# Sheet1.net
KiCad netlist of a schematic drawn in Altium Designer
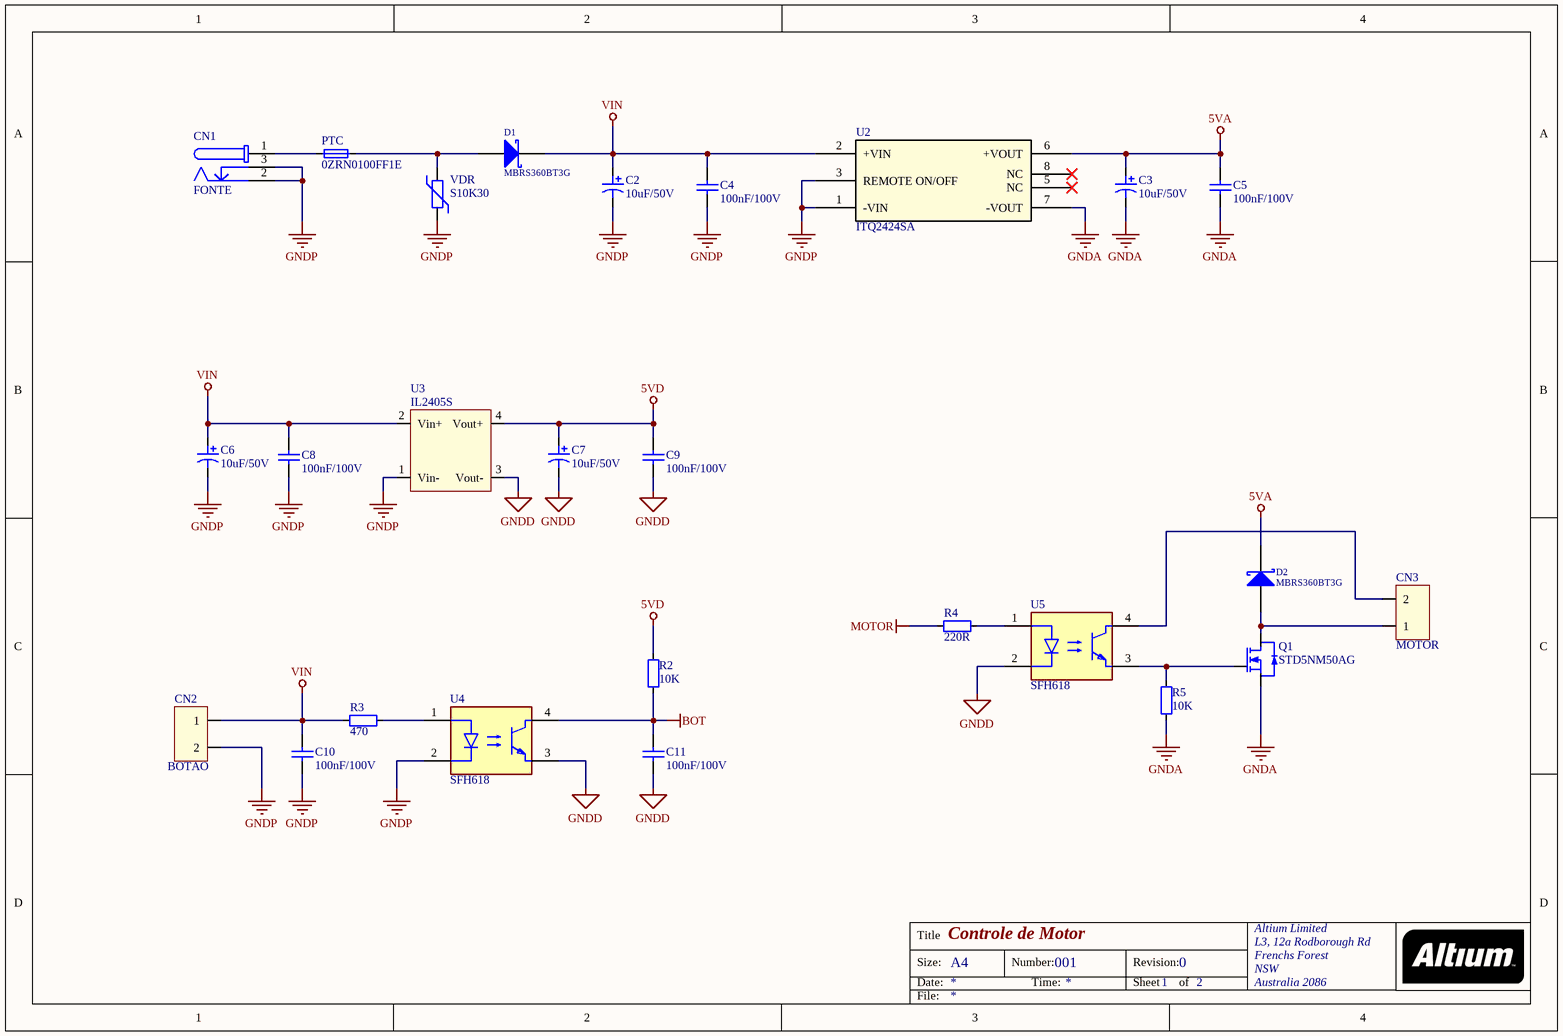
[diagram p0: Sheet1.SchDoc]

(export (version "E")
  (design (tool "Eeschema 10.0.6"))
  (components
    (comp (ref "C2")
      (value "10uF/50V")
      (footprint "CapE SMD D6.3 L5.8")
      (description "Capacitor Eletrolítico Radial SMD")
      (libsource (lib "Schlib") (part "Cap Eletrolitico"))
    )
    (comp (ref "C3")
      (value "10uF/50V")
      (footprint "CapE SMD D6.3 L5.8")
      (description "Capacitor Eletrolítico Radial SMD")
      (libsource (lib "Schlib") (part "Cap Eletrolitico"))
    )
    (comp (ref "C4")
      (value "100nF/100V")
      (footprint "0603C-GENERIC")
      (description "Capacitor Cerâmico SMD")
      (libsource (lib "Schlib") (part "Cap Ceramico SMD"))
    )
    (comp (ref "C5")
      (value "100nF/100V")
      (footprint "0603C-GENERIC")
      (description "Capacitor Cerâmico SMD")
      (libsource (lib "Schlib") (part "Cap Ceramico SMD"))
    )
    (comp (ref "C6")
      (value "10uF/50V")
      (footprint "CapE SMD D6.3 L5.8")
      (description "Capacitor Eletrolítico Radial SMD")
      (libsource (lib "Schlib") (part "Cap Eletrolitico"))
    )
    (comp (ref "C7")
      (value "10uF/50V")
      (footprint "CapE SMD D6.3 L5.8")
      (description "Capacitor Eletrolítico Radial SMD")
      (libsource (lib "Schlib") (part "Cap Eletrolitico"))
    )
    (comp (ref "C8")
      (value "100nF/100V")
      (footprint "0603C-GENERIC")
      (description "Capacitor Cerâmico SMD")
      (libsource (lib "Schlib") (part "Cap Ceramico SMD"))
    )
    (comp (ref "C9")
      (value "100nF/100V")
      (footprint "0603C-GENERIC")
      (description "Capacitor Cerâmico SMD")
      (libsource (lib "Schlib") (part "Cap Ceramico SMD"))
    )
    (comp (ref "C10")
      (value "100nF/100V")
      (footprint "0603C-GENERIC")
      (description "Capacitor Cerâmico SMD")
      (libsource (lib "Schlib") (part "Cap Ceramico SMD"))
    )
    (comp (ref "C11")
      (value "100nF/100V")
      (footprint "0603C-GENERIC")
      (description "Capacitor Cerâmico SMD")
      (libsource (lib "Schlib") (part "Cap Ceramico SMD"))
    )
    (comp (ref "CN1")
      (value "FONTE")
      (footprint "Power Jack 694106301002")
      (description "DC Power Jack")
      (fields (field (name "PART NUMBER") "694106301002"))
      (libsource (lib "PUR Conectores") (part "DC Power Jack"))
    )
    (comp (ref "CN2")
      (value "BORNE")
      (footprint "AKZ700/2")
      (description "2 pinos")
      (libsource (lib "") (part "1x2 Pinos_1"))
    )
    (comp (ref "CN3")
      (value "BORNE")
      (footprint "AKZ700/2")
      (description "2 pinos")
      (libsource (lib "PUR Conectores") (part "1x2 Pinos"))
    )
    (comp (ref "D1")
      (value "MBRS360BT3G")
      (footprint "DO-214AA(SMB)")
      (description "Schottky Barrier Diode")
      (libsource (lib "Schlib") (part "BAT54"))
    )
    (comp (ref "D2")
      (value "MBRS360BT3G")
      (footprint "DO-214AA(SMB)")
      (description "Schottky Barrier Diode")
      (libsource (lib "Schlib") (part "BAT54"))
    )
    (comp (ref "PTC")
      (value "0ZRN0100FF1E")
      (footprint "PTC LVR")
      (description "Fusível Thermistor PTC")
      (libsource (lib "PUR Geral") (part "LVR008N"))
    )
    (comp (ref "Q1")
      (value "STD5NM50AG")
      (footprint "DPAK-3_ONS")
      (description "Transistor N-Channel")
      (libsource (lib "PUR Geral") (part "BSS138"))
    )
    (comp (ref "R2")
      (value "10K")
      (footprint "0603R")
      (description "Resistor Metal Filme")
      (libsource (lib "") (part "Res SMD 1206_2"))
    )
    (comp (ref "R3")
      (value "470")
      (footprint "Res 1206")
      (description "Resistor Metal Filme")
      (libsource (lib "") (part "Res SMD 1206_1"))
    )
    (comp (ref "R4")
      (value "220R")
      (footprint "0603R")
      (description "Resistor Metal Filme")
      (libsource (lib "Database_PUR") (part "Res SMD 1206"))
    )
    (comp (ref "R5")
      (value "10K")
      (footprint "0603R")
      (description "Resistor Metal Filme")
      (libsource (lib "") (part "Res SMD 1206_2"))
    )
    (comp (ref "U2")
      (value "ITQ2424SA")
      (footprint "SIP8_ITQ2424_XPR")
      (description "No Description Available")
      (fields (field (name "COPYRIGHT") "Copyright (C) 2026 Ultra Librarian. All rights reserved."))
      (libsource (lib "Schlib") (part "ITQ2424SA"))
    )
    (comp (ref "U3")
      (value "IL2405S")
      (footprint "IL SERIES")
      (description "Conversor DC/DC 2W")
      (fields (field (name "PART NUMBER") "E2CONV0000006"))
      (libsource (lib "PUR Geral") (part "IL2405S"))
    )
    (comp (ref "U4")
      (value "SFH618")
      (footprint "FP-83911-MFG")
      (description "Optocoupler Dc-in 1-CH Transistor Dc-out 4-PIN PDIP SMD T/r")
      (libsource (lib "PUR Equipamentos Industriais") (part "aa71ce9e162979105c9edb12a8cdbcc"))
    )
    (comp (ref "U5")
      (value "SFH618")
      (footprint "FP-83911-MFG")
      (description "Optocoupler Dc-in 1-CH Transistor Dc-out 4-PIN PDIP SMD T/r")
      (libsource (lib "PUR Equipamentos Industriais") (part "aa71ce9e162979105c9edb12a8cdbcc"))
    )
    (comp (ref "VDR")
      (value "S10K30")
      (footprint "VDR D12H14.5-7.5")
      (description "Varistor 30VAC/48VDC")
      (libsource (lib "PUR Geral") (part "VDR 1000L160"))
    )
  )
  (nets
    (net (code "1") (name "5VA") (class "Default")
      (node (ref "C3") (pin "1") (pinfunction "+_1") (pintype "passive"))
      (node (ref "C5") (pin "2") (pinfunction "2_2") (pintype "passive"))
      (node (ref "D2") (pin "2") (pinfunction "K_2") (pintype "passive"))
      (node (ref "U2") (pin "6") (pinfunction "+VOUT_6") (pintype "power_in"))
    )
    (net (code "2") (name "5VD") (class "Default")
      (node (ref "C7") (pin "1") (pinfunction "+_1") (pintype "passive"))
      (node (ref "C9") (pin "2") (pinfunction "2_2") (pintype "passive"))
      (node (ref "R2") (pin "1") (pinfunction "1_1") (pintype "passive"))
      (node (ref "U3") (pin "4") (pinfunction "Vout+_4") (pintype "passive"))
    )
    (net (code "3") (name "BOT") (class "Default")
      (node (ref "C11") (pin "2") (pinfunction "2_2") (pintype "passive"))
      (node (ref "R2") (pin "2") (pinfunction "2_2") (pintype "passive"))
      (node (ref "U4") (pin "4") (pinfunction "C_4") (pintype "passive"))
    )
    (net (code "4") (name "GNDA") (class "Default")
      (node (ref "C3") (pin "2") (pinfunction "-_2") (pintype "passive"))
      (node (ref "C5") (pin "1") (pinfunction "1_1") (pintype "passive"))
      (node (ref "Q1") (pin "2") (pinfunction "S_2") (pintype "passive"))
      (node (ref "R5") (pin "2") (pinfunction "2_2") (pintype "passive"))
      (node (ref "U2") (pin "7") (pinfunction "-VOUT_7") (pintype "power_in"))
    )
    (net (code "5") (name "GNDD") (class "Default")
      (node (ref "C11") (pin "1") (pinfunction "1_1") (pintype "passive"))
      (node (ref "C7") (pin "2") (pinfunction "-_2") (pintype "passive"))
      (node (ref "C9") (pin "1") (pinfunction "1_1") (pintype "passive"))
      (node (ref "U3") (pin "3") (pinfunction "Vout-_3") (pintype "passive"))
      (node (ref "U4") (pin "3") (pinfunction "E_3") (pintype "passive"))
      (node (ref "U5") (pin "2") (pinfunction "C_2") (pintype "passive"))
    )
    (net (code "6") (name "GNDP") (class "Default")
      (node (ref "C10") (pin "1") (pinfunction "1_1") (pintype "passive"))
      (node (ref "C2") (pin "2") (pinfunction "-_2") (pintype "passive"))
      (node (ref "C4") (pin "1") (pinfunction "1_1") (pintype "passive"))
      (node (ref "C6") (pin "2") (pinfunction "-_2") (pintype "passive"))
      (node (ref "C8") (pin "1") (pinfunction "1_1") (pintype "passive"))
      (node (ref "CN1") (pin "2") (pinfunction "2_2") (pintype "passive"))
      (node (ref "CN1") (pin "3") (pinfunction "3_3") (pintype "passive"))
      (node (ref "CN2") (pin "2") (pinfunction "2_2") (pintype "passive"))
      (node (ref "U2") (pin "1") (pinfunction "-VIN_1") (pintype "power_in"))
      (node (ref "U2") (pin "3") (pinfunction "REMOTE_ON/OFF_3") (pintype "passive"))
      (node (ref "U3") (pin "1") (pinfunction "Vin-_1") (pintype "passive"))
      (node (ref "U4") (pin "2") (pinfunction "C_2") (pintype "passive"))
      (node (ref "VDR") (pin "1") (pinfunction "1_1") (pintype "passive"))
    )
    (net (code "7") (name "MOTOR") (class "Default")
      (node (ref "R4") (pin "1") (pinfunction "1_1") (pintype "passive"))
    )
    (net (code "8") (name "Net-(CN1-Pad1)") (class "Default")
      (node (ref "CN1") (pin "1") (pinfunction "1_1") (pintype "passive"))
      (node (ref "PTC") (pin "1") (pintype "passive"))
    )
    (net (code "9") (name "Net-(CN3-Pad2)") (class "Default")
      (node (ref "CN3") (pin "2") (pinfunction "2_2") (pintype "passive"))
      (node (ref "U5") (pin "4") (pinfunction "C_4") (pintype "passive"))
    )
    (net (code "10") (name "Net-(D1-A)") (class "Default")
      (node (ref "D1") (pin "1") (pinfunction "A_1") (pintype "passive"))
      (node (ref "PTC") (pin "2") (pintype "passive"))
      (node (ref "VDR") (pin "2") (pinfunction "2_2") (pintype "passive"))
    )
    (net (code "11") (name "Net-(D2-A)") (class "Default")
      (node (ref "CN3") (pin "1") (pinfunction "1_1") (pintype "passive"))
      (node (ref "D2") (pin "1") (pinfunction "A_1") (pintype "passive"))
      (node (ref "Q1") (pin "3") (pinfunction "D_3") (pintype "passive"))
    )
    (net (code "12") (name "Net-(Q1-G)") (class "Default")
      (node (ref "Q1") (pin "1") (pinfunction "G_1") (pintype "passive"))
      (node (ref "R5") (pin "1") (pinfunction "1_1") (pintype "passive"))
      (node (ref "U5") (pin "3") (pinfunction "E_3") (pintype "passive"))
    )
    (net (code "13") (name "Net-(U4-A)") (class "Default")
      (node (ref "R3") (pin "1") (pinfunction "1_1") (pintype "passive"))
      (node (ref "U4") (pin "1") (pinfunction "A_1") (pintype "passive"))
    )
    (net (code "14") (name "Net-(U5-A)") (class "Default")
      (node (ref "R4") (pin "2") (pinfunction "2_2") (pintype "passive"))
      (node (ref "U5") (pin "1") (pinfunction "A_1") (pintype "passive"))
    )
    (net (code "15") (name "VIN") (class "Default")
      (node (ref "C10") (pin "2") (pinfunction "2_2") (pintype "passive"))
      (node (ref "C2") (pin "1") (pinfunction "+_1") (pintype "passive"))
      (node (ref "C4") (pin "2") (pinfunction "2_2") (pintype "passive"))
      (node (ref "C6") (pin "1") (pinfunction "+_1") (pintype "passive"))
      (node (ref "C8") (pin "2") (pinfunction "2_2") (pintype "passive"))
      (node (ref "CN2") (pin "1") (pinfunction "1_1") (pintype "passive"))
      (node (ref "D1") (pin "2") (pinfunction "K_2") (pintype "passive"))
      (node (ref "R3") (pin "2") (pinfunction "2_2") (pintype "passive"))
      (node (ref "U2") (pin "2") (pinfunction "+VIN_2") (pintype "power_in"))
      (node (ref "U3") (pin "2") (pinfunction "Vin+_2") (pintype "passive"))
    )
    (net (code "16") (name "unconnected-(U2-NC-Pad5)") (class "Default")
      (node (ref "U2") (pin "5") (pinfunction "NC_5") (pintype "passive+no_connect"))
    )
    (net (code "17") (name "unconnected-(U2-NC-Pad8)") (class "Default")
      (node (ref "U2") (pin "8") (pinfunction "NC_8") (pintype "passive+no_connect"))
    )
  )
)
